# Main.net
KiCad netlist of a schematic drawn in Altium Designer
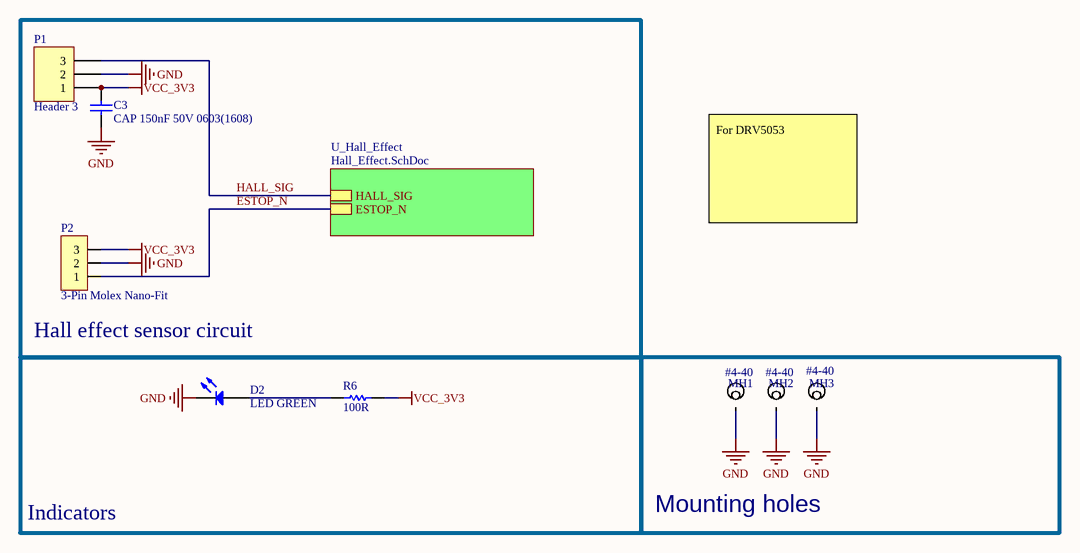
[diagram p0: Main.SchDoc]

(export (version "E")
  (design (tool "Eeschema 10.0.6"))
  (components
    (comp (ref "C3")
      (value "CAP 150nF 50V 0603(1608)")
      (footprint "CAPC0603(1608)100_M")
      (description "CAP 150nF 50V -20% to +80% 0603 (1608 Metric) Thickness 1mm SMD")
      (fields (field (name "TOLERANCE") "-20% to +80%"))
      (libsource (lib "Altium Content Vault") (part "CAP"))
    )
    (comp (ref "D2")
      (value "LED GREEN")
      (footprint "LED_0805")
      (description "led")
      (fields
        (field (name "MANUFACTURER") "Lite-On Inc.")
        (field (name "MANUFACTURER PART NUMBER") "LTST-C171KGKT")
      )
      (libsource (lib "CMR_Miscellaneous_Devices") (part "LED0"))
    )
    (comp (ref "MH1")
      (value "#4-40")
      (footprint "Mounting Hole #4-40")
      (description "Mounting Hole for ANSI #4-40 w/ Flat Washer, Loose Fit")
      (libsource (lib "CMR_PCB_Components") (part "Mounting Hole #4-40, Loose Fit"))
    )
    (comp (ref "MH2")
      (value "#4-40")
      (footprint "Mounting Hole #4-40")
      (description "Mounting Hole for ANSI #4-40 w/ Flat Washer, Loose Fit")
      (libsource (lib "CMR_PCB_Components") (part "Mounting Hole #4-40, Loose Fit"))
    )
    (comp (ref "MH3")
      (value "#4-40")
      (footprint "Mounting Hole #4-40")
      (description "Mounting Hole for ANSI #4-40 w/ Flat Washer, Loose Fit")
      (libsource (lib "CMR_PCB_Components") (part "Mounting Hole #4-40, Loose Fit"))
    )
    (comp (ref "P1")
      (value "Header 3")
      (footprint "HDR1X3")
      (description "Header, 3-Pin")
      (fields (field (name "PUBLISHER") "Altium Limited"))
      (libsource (lib "Miscellaneous Connectors") (part "Header 3"))
    )
    (comp (ref "P2")
      (value "3-Pin Molex Nano-Fit")
      (footprint "MOLEX NANO-FIT 1X3")
      (description "NanoFit RA Hdr TH SR 3Ckt")
      (fields (field (name "MANUFACTURER") "Molex") (field (name "PART NUMBER") "105313-1204"))
      (libsource (lib "CMR_Connectors") (part "3-Pin Nano-Fit"))
    )
    (comp (ref "R6")
      (value "100R")
      (footprint "RESC0603(1608)_N")
      (description "100R 0.1W 5% 0603 (1608 Metric)  SMD")
      (fields (field (name "TOLERANCE") "5 %") (field (name "POWER") "0.1 W"))
      (libsource (lib "Altium Content Vault") (part "RES"))
    )
  )
  (nets
    (net (code "1") (name "/ESTOP_N") (class "Default")
      (node (ref "P2") (pin "1") (pinfunction "1_1") (pintype "passive"))
    )
    (net (code "2") (name "/HALL_SIG") (class "Default")
      (node (ref "P1") (pin "3") (pinfunction "3_3") (pintype "passive"))
    )
    (net (code "3") (name "GND") (class "Default")
      (node (ref "C3") (pin "2") (pinfunction "2_2") (pintype "passive"))
      (node (ref "D2") (pin "1") (pinfunction "K_1") (pintype "passive"))
      (node (ref "MH1") (pin "0") (pinfunction "0_0") (pintype "passive"))
      (node (ref "MH2") (pin "0") (pinfunction "0_0") (pintype "passive"))
      (node (ref "MH3") (pin "0") (pinfunction "0_0") (pintype "passive"))
      (node (ref "P1") (pin "2") (pinfunction "2_2") (pintype "passive"))
      (node (ref "P2") (pin "2") (pinfunction "2_2") (pintype "passive"))
    )
    (net (code "4") (name "Net-(D2-A)") (class "Default")
      (node (ref "D2") (pin "2") (pinfunction "A_2") (pintype "passive"))
      (node (ref "R6") (pin "1") (pinfunction "1_1") (pintype "passive"))
    )
    (net (code "5") (name "VCC_3V3") (class "Default")
      (node (ref "C3") (pin "1") (pinfunction "1_1") (pintype "passive"))
      (node (ref "P1") (pin "1") (pinfunction "1_1") (pintype "passive"))
      (node (ref "P2") (pin "3") (pinfunction "3_3") (pintype "passive"))
      (node (ref "R6") (pin "2") (pinfunction "2_2") (pintype "passive"))
    )
  )
)
